# SCH_HackPack_2024-05-12.net
KiCad netlist of a schematic drawn in EasyEDA
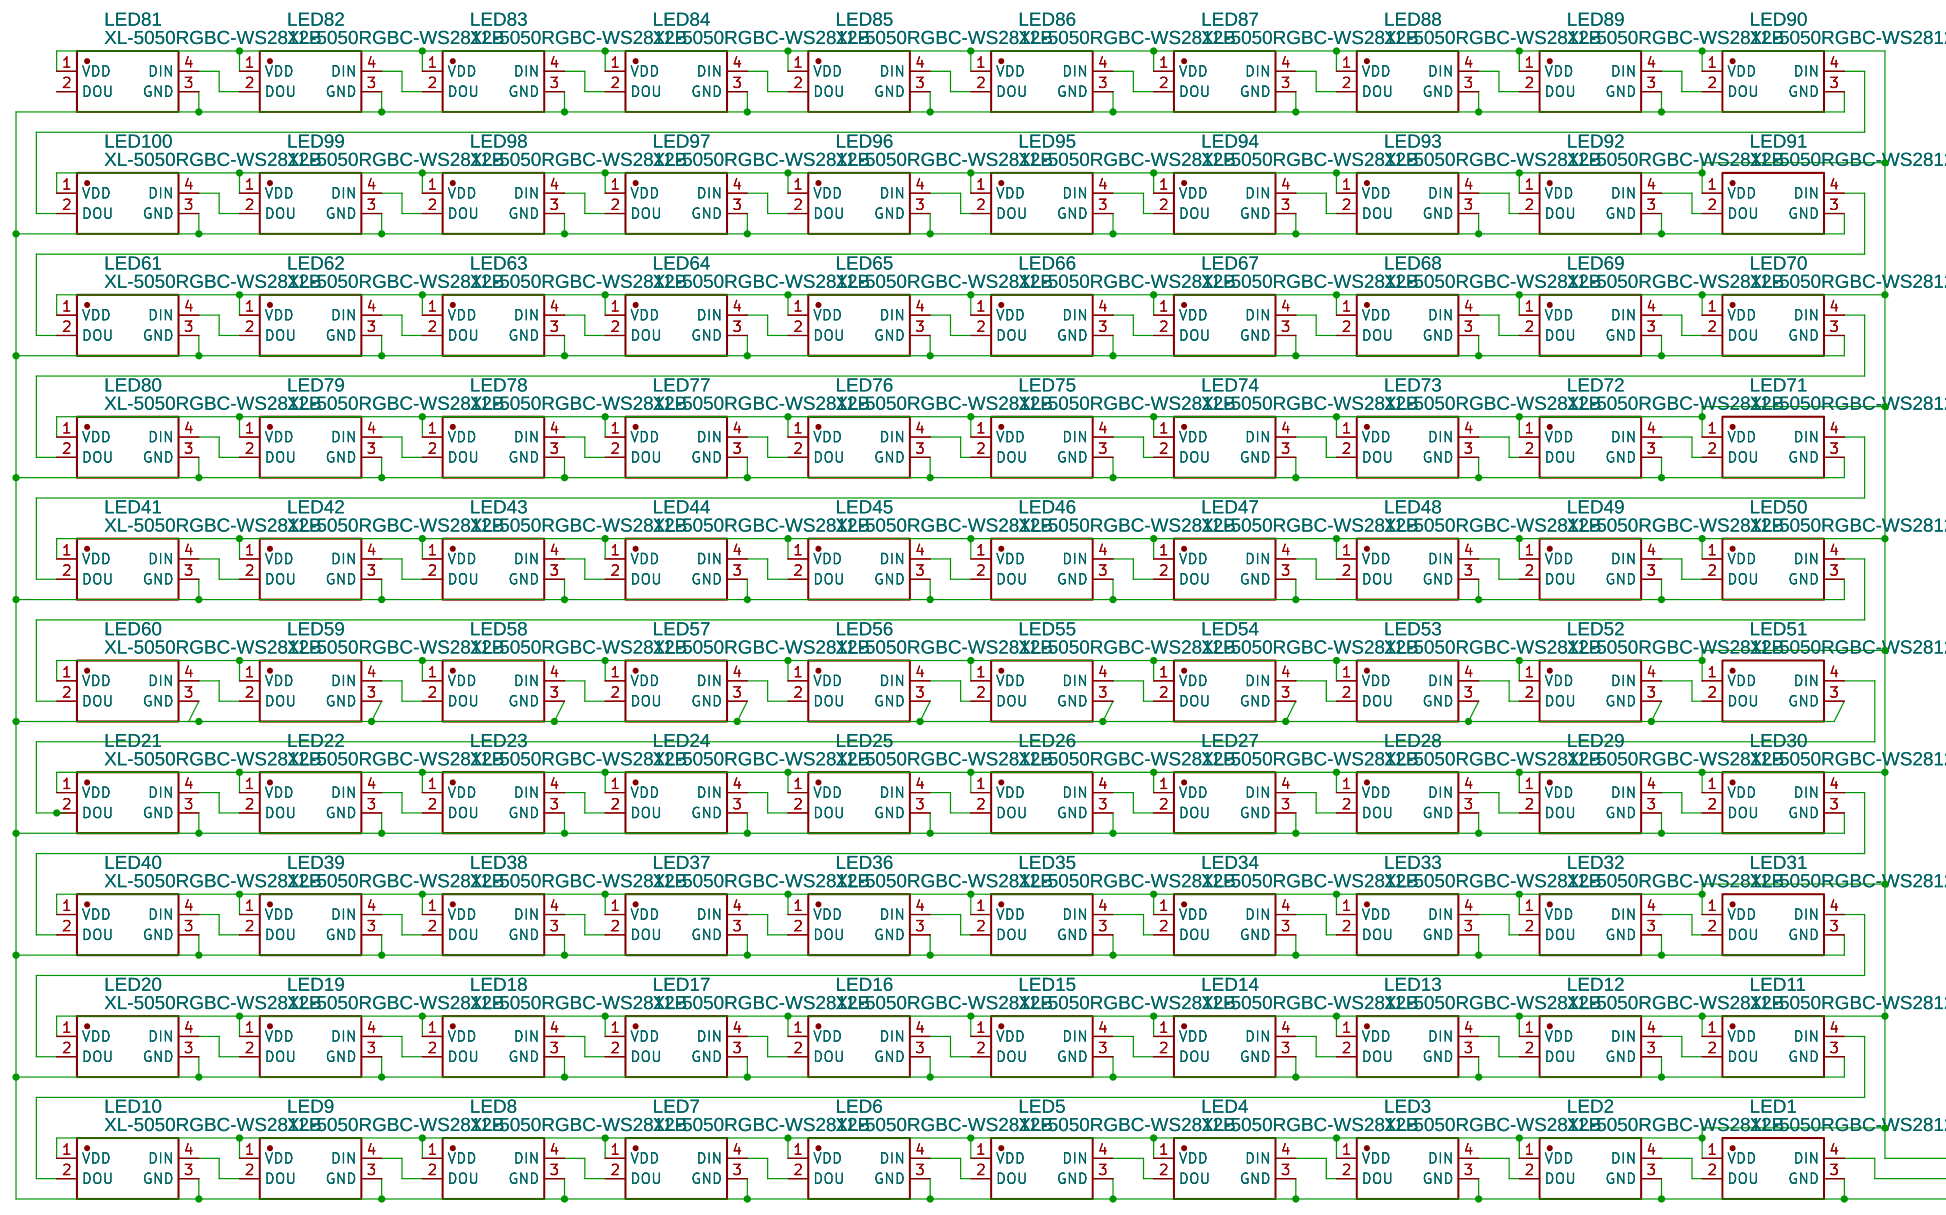
[diagram p0: schematic sheet]

(export (version "E")
  (design (tool "Eeschema 10.0.6"))
  (components
    (comp (ref "LED1")
      (value "XL-5050RGBC-WS2812B")
      (fields (field (name "Manufacturer") "XINGLIGHT(成兴光)"))
      (libsource (lib "") (part "XL-5050RGBC-WS2812B"))
    )
    (comp (ref "LED2")
      (value "XL-5050RGBC-WS2812B")
      (fields (field (name "Manufacturer") "XINGLIGHT(成兴光)"))
      (libsource (lib "") (part "XL-5050RGBC-WS2812B"))
    )
    (comp (ref "LED3")
      (value "XL-5050RGBC-WS2812B")
      (fields (field (name "Manufacturer") "XINGLIGHT(成兴光)"))
      (libsource (lib "") (part "XL-5050RGBC-WS2812B"))
    )
    (comp (ref "LED4")
      (value "XL-5050RGBC-WS2812B")
      (fields (field (name "Manufacturer") "XINGLIGHT(成兴光)"))
      (libsource (lib "") (part "XL-5050RGBC-WS2812B"))
    )
    (comp (ref "LED5")
      (value "XL-5050RGBC-WS2812B")
      (fields (field (name "Manufacturer") "XINGLIGHT(成兴光)"))
      (libsource (lib "") (part "XL-5050RGBC-WS2812B"))
    )
    (comp (ref "LED6")
      (value "XL-5050RGBC-WS2812B")
      (fields (field (name "Manufacturer") "XINGLIGHT(成兴光)"))
      (libsource (lib "") (part "XL-5050RGBC-WS2812B"))
    )
    (comp (ref "LED7")
      (value "XL-5050RGBC-WS2812B")
      (fields (field (name "Manufacturer") "XINGLIGHT(成兴光)"))
      (libsource (lib "") (part "XL-5050RGBC-WS2812B"))
    )
    (comp (ref "LED8")
      (value "XL-5050RGBC-WS2812B")
      (fields (field (name "Manufacturer") "XINGLIGHT(成兴光)"))
      (libsource (lib "") (part "XL-5050RGBC-WS2812B"))
    )
    (comp (ref "LED9")
      (value "XL-5050RGBC-WS2812B")
      (fields (field (name "Manufacturer") "XINGLIGHT(成兴光)"))
      (libsource (lib "") (part "XL-5050RGBC-WS2812B"))
    )
    (comp (ref "LED10")
      (value "XL-5050RGBC-WS2812B")
      (fields (field (name "Manufacturer") "XINGLIGHT(成兴光)"))
      (libsource (lib "") (part "XL-5050RGBC-WS2812B"))
    )
    (comp (ref "LED11")
      (value "XL-5050RGBC-WS2812B")
      (fields (field (name "Manufacturer") "XINGLIGHT(成兴光)"))
      (libsource (lib "") (part "XL-5050RGBC-WS2812B"))
    )
    (comp (ref "LED12")
      (value "XL-5050RGBC-WS2812B")
      (fields (field (name "Manufacturer") "XINGLIGHT(成兴光)"))
      (libsource (lib "") (part "XL-5050RGBC-WS2812B"))
    )
    (comp (ref "LED13")
      (value "XL-5050RGBC-WS2812B")
      (fields (field (name "Manufacturer") "XINGLIGHT(成兴光)"))
      (libsource (lib "") (part "XL-5050RGBC-WS2812B"))
    )
    (comp (ref "LED14")
      (value "XL-5050RGBC-WS2812B")
      (fields (field (name "Manufacturer") "XINGLIGHT(成兴光)"))
      (libsource (lib "") (part "XL-5050RGBC-WS2812B"))
    )
    (comp (ref "LED15")
      (value "XL-5050RGBC-WS2812B")
      (fields (field (name "Manufacturer") "XINGLIGHT(成兴光)"))
      (libsource (lib "") (part "XL-5050RGBC-WS2812B"))
    )
    (comp (ref "LED16")
      (value "XL-5050RGBC-WS2812B")
      (fields (field (name "Manufacturer") "XINGLIGHT(成兴光)"))
      (libsource (lib "") (part "XL-5050RGBC-WS2812B"))
    )
    (comp (ref "LED17")
      (value "XL-5050RGBC-WS2812B")
      (fields (field (name "Manufacturer") "XINGLIGHT(成兴光)"))
      (libsource (lib "") (part "XL-5050RGBC-WS2812B"))
    )
    (comp (ref "LED18")
      (value "XL-5050RGBC-WS2812B")
      (fields (field (name "Manufacturer") "XINGLIGHT(成兴光)"))
      (libsource (lib "") (part "XL-5050RGBC-WS2812B"))
    )
    (comp (ref "LED19")
      (value "XL-5050RGBC-WS2812B")
      (fields (field (name "Manufacturer") "XINGLIGHT(成兴光)"))
      (libsource (lib "") (part "XL-5050RGBC-WS2812B"))
    )
    (comp (ref "LED20")
      (value "XL-5050RGBC-WS2812B")
      (fields (field (name "Manufacturer") "XINGLIGHT(成兴光)"))
      (libsource (lib "") (part "XL-5050RGBC-WS2812B"))
    )
    (comp (ref "LED21")
      (value "XL-5050RGBC-WS2812B")
      (fields (field (name "Manufacturer") "XINGLIGHT(成兴光)"))
      (libsource (lib "") (part "XL-5050RGBC-WS2812B"))
    )
    (comp (ref "LED22")
      (value "XL-5050RGBC-WS2812B")
      (fields (field (name "Manufacturer") "XINGLIGHT(成兴光)"))
      (libsource (lib "") (part "XL-5050RGBC-WS2812B"))
    )
    (comp (ref "LED23")
      (value "XL-5050RGBC-WS2812B")
      (fields (field (name "Manufacturer") "XINGLIGHT(成兴光)"))
      (libsource (lib "") (part "XL-5050RGBC-WS2812B"))
    )
    (comp (ref "LED24")
      (value "XL-5050RGBC-WS2812B")
      (fields (field (name "Manufacturer") "XINGLIGHT(成兴光)"))
      (libsource (lib "") (part "XL-5050RGBC-WS2812B"))
    )
    (comp (ref "LED25")
      (value "XL-5050RGBC-WS2812B")
      (fields (field (name "Manufacturer") "XINGLIGHT(成兴光)"))
      (libsource (lib "") (part "XL-5050RGBC-WS2812B"))
    )
    (comp (ref "LED26")
      (value "XL-5050RGBC-WS2812B")
      (fields (field (name "Manufacturer") "XINGLIGHT(成兴光)"))
      (libsource (lib "") (part "XL-5050RGBC-WS2812B"))
    )
    (comp (ref "LED27")
      (value "XL-5050RGBC-WS2812B")
      (fields (field (name "Manufacturer") "XINGLIGHT(成兴光)"))
      (libsource (lib "") (part "XL-5050RGBC-WS2812B"))
    )
    (comp (ref "LED28")
      (value "XL-5050RGBC-WS2812B")
      (fields (field (name "Manufacturer") "XINGLIGHT(成兴光)"))
      (libsource (lib "") (part "XL-5050RGBC-WS2812B"))
    )
    (comp (ref "LED29")
      (value "XL-5050RGBC-WS2812B")
      (fields (field (name "Manufacturer") "XINGLIGHT(成兴光)"))
      (libsource (lib "") (part "XL-5050RGBC-WS2812B"))
    )
    (comp (ref "LED30")
      (value "XL-5050RGBC-WS2812B")
      (fields (field (name "Manufacturer") "XINGLIGHT(成兴光)"))
      (libsource (lib "") (part "XL-5050RGBC-WS2812B"))
    )
    (comp (ref "LED31")
      (value "XL-5050RGBC-WS2812B")
      (fields (field (name "Manufacturer") "XINGLIGHT(成兴光)"))
      (libsource (lib "") (part "XL-5050RGBC-WS2812B"))
    )
    (comp (ref "LED32")
      (value "XL-5050RGBC-WS2812B")
      (fields (field (name "Manufacturer") "XINGLIGHT(成兴光)"))
      (libsource (lib "") (part "XL-5050RGBC-WS2812B"))
    )
    (comp (ref "LED33")
      (value "XL-5050RGBC-WS2812B")
      (fields (field (name "Manufacturer") "XINGLIGHT(成兴光)"))
      (libsource (lib "") (part "XL-5050RGBC-WS2812B"))
    )
    (comp (ref "LED34")
      (value "XL-5050RGBC-WS2812B")
      (fields (field (name "Manufacturer") "XINGLIGHT(成兴光)"))
      (libsource (lib "") (part "XL-5050RGBC-WS2812B"))
    )
    (comp (ref "LED35")
      (value "XL-5050RGBC-WS2812B")
      (fields (field (name "Manufacturer") "XINGLIGHT(成兴光)"))
      (libsource (lib "") (part "XL-5050RGBC-WS2812B"))
    )
    (comp (ref "LED36")
      (value "XL-5050RGBC-WS2812B")
      (fields (field (name "Manufacturer") "XINGLIGHT(成兴光)"))
      (libsource (lib "") (part "XL-5050RGBC-WS2812B"))
    )
    (comp (ref "LED37")
      (value "XL-5050RGBC-WS2812B")
      (fields (field (name "Manufacturer") "XINGLIGHT(成兴光)"))
      (libsource (lib "") (part "XL-5050RGBC-WS2812B"))
    )
    (comp (ref "LED38")
      (value "XL-5050RGBC-WS2812B")
      (fields (field (name "Manufacturer") "XINGLIGHT(成兴光)"))
      (libsource (lib "") (part "XL-5050RGBC-WS2812B"))
    )
    (comp (ref "LED39")
      (value "XL-5050RGBC-WS2812B")
      (fields (field (name "Manufacturer") "XINGLIGHT(成兴光)"))
      (libsource (lib "") (part "XL-5050RGBC-WS2812B"))
    )
    (comp (ref "LED40")
      (value "XL-5050RGBC-WS2812B")
      (fields (field (name "Manufacturer") "XINGLIGHT(成兴光)"))
      (libsource (lib "") (part "XL-5050RGBC-WS2812B"))
    )
    (comp (ref "LED41")
      (value "XL-5050RGBC-WS2812B")
      (fields (field (name "Manufacturer") "XINGLIGHT(成兴光)"))
      (libsource (lib "") (part "XL-5050RGBC-WS2812B"))
    )
    (comp (ref "LED42")
      (value "XL-5050RGBC-WS2812B")
      (fields (field (name "Manufacturer") "XINGLIGHT(成兴光)"))
      (libsource (lib "") (part "XL-5050RGBC-WS2812B"))
    )
    (comp (ref "LED43")
      (value "XL-5050RGBC-WS2812B")
      (fields (field (name "Manufacturer") "XINGLIGHT(成兴光)"))
      (libsource (lib "") (part "XL-5050RGBC-WS2812B"))
    )
    (comp (ref "LED44")
      (value "XL-5050RGBC-WS2812B")
      (fields (field (name "Manufacturer") "XINGLIGHT(成兴光)"))
      (libsource (lib "") (part "XL-5050RGBC-WS2812B"))
    )
    (comp (ref "LED45")
      (value "XL-5050RGBC-WS2812B")
      (fields (field (name "Manufacturer") "XINGLIGHT(成兴光)"))
      (libsource (lib "") (part "XL-5050RGBC-WS2812B"))
    )
    (comp (ref "LED46")
      (value "XL-5050RGBC-WS2812B")
      (fields (field (name "Manufacturer") "XINGLIGHT(成兴光)"))
      (libsource (lib "") (part "XL-5050RGBC-WS2812B"))
    )
    (comp (ref "LED47")
      (value "XL-5050RGBC-WS2812B")
      (fields (field (name "Manufacturer") "XINGLIGHT(成兴光)"))
      (libsource (lib "") (part "XL-5050RGBC-WS2812B"))
    )
    (comp (ref "LED48")
      (value "XL-5050RGBC-WS2812B")
      (fields (field (name "Manufacturer") "XINGLIGHT(成兴光)"))
      (libsource (lib "") (part "XL-5050RGBC-WS2812B"))
    )
    (comp (ref "LED49")
      (value "XL-5050RGBC-WS2812B")
      (fields (field (name "Manufacturer") "XINGLIGHT(成兴光)"))
      (libsource (lib "") (part "XL-5050RGBC-WS2812B"))
    )
    (comp (ref "LED50")
      (value "XL-5050RGBC-WS2812B")
      (fields (field (name "Manufacturer") "XINGLIGHT(成兴光)"))
      (libsource (lib "") (part "XL-5050RGBC-WS2812B"))
    )
    (comp (ref "LED51")
      (value "XL-5050RGBC-WS2812B")
      (fields (field (name "Manufacturer") "XINGLIGHT(成兴光)"))
      (libsource (lib "") (part "XL-5050RGBC-WS2812B"))
    )
    (comp (ref "LED52")
      (value "XL-5050RGBC-WS2812B")
      (fields (field (name "Manufacturer") "XINGLIGHT(成兴光)"))
      (libsource (lib "") (part "XL-5050RGBC-WS2812B"))
    )
    (comp (ref "LED53")
      (value "XL-5050RGBC-WS2812B")
      (fields (field (name "Manufacturer") "XINGLIGHT(成兴光)"))
      (libsource (lib "") (part "XL-5050RGBC-WS2812B"))
    )
    (comp (ref "LED54")
      (value "XL-5050RGBC-WS2812B")
      (fields (field (name "Manufacturer") "XINGLIGHT(成兴光)"))
      (libsource (lib "") (part "XL-5050RGBC-WS2812B"))
    )
    (comp (ref "LED55")
      (value "XL-5050RGBC-WS2812B")
      (fields (field (name "Manufacturer") "XINGLIGHT(成兴光)"))
      (libsource (lib "") (part "XL-5050RGBC-WS2812B"))
    )
    (comp (ref "LED56")
      (value "XL-5050RGBC-WS2812B")
      (fields (field (name "Manufacturer") "XINGLIGHT(成兴光)"))
      (libsource (lib "") (part "XL-5050RGBC-WS2812B"))
    )
    (comp (ref "LED57")
      (value "XL-5050RGBC-WS2812B")
      (fields (field (name "Manufacturer") "XINGLIGHT(成兴光)"))
      (libsource (lib "") (part "XL-5050RGBC-WS2812B"))
    )
    (comp (ref "LED58")
      (value "XL-5050RGBC-WS2812B")
      (fields (field (name "Manufacturer") "XINGLIGHT(成兴光)"))
      (libsource (lib "") (part "XL-5050RGBC-WS2812B"))
    )
    (comp (ref "LED59")
      (value "XL-5050RGBC-WS2812B")
      (fields (field (name "Manufacturer") "XINGLIGHT(成兴光)"))
      (libsource (lib "") (part "XL-5050RGBC-WS2812B"))
    )
    (comp (ref "LED60")
      (value "XL-5050RGBC-WS2812B")
      (fields (field (name "Manufacturer") "XINGLIGHT(成兴光)"))
      (libsource (lib "") (part "XL-5050RGBC-WS2812B"))
    )
    (comp (ref "LED61")
      (value "XL-5050RGBC-WS2812B")
      (fields (field (name "Manufacturer") "XINGLIGHT(成兴光)"))
      (libsource (lib "") (part "XL-5050RGBC-WS2812B"))
    )
    (comp (ref "LED62")
      (value "XL-5050RGBC-WS2812B")
      (fields (field (name "Manufacturer") "XINGLIGHT(成兴光)"))
      (libsource (lib "") (part "XL-5050RGBC-WS2812B"))
    )
    (comp (ref "LED63")
      (value "XL-5050RGBC-WS2812B")
      (fields (field (name "Manufacturer") "XINGLIGHT(成兴光)"))
      (libsource (lib "") (part "XL-5050RGBC-WS2812B"))
    )
    (comp (ref "LED64")
      (value "XL-5050RGBC-WS2812B")
      (fields (field (name "Manufacturer") "XINGLIGHT(成兴光)"))
      (libsource (lib "") (part "XL-5050RGBC-WS2812B"))
    )
    (comp (ref "LED65")
      (value "XL-5050RGBC-WS2812B")
      (fields (field (name "Manufacturer") "XINGLIGHT(成兴光)"))
      (libsource (lib "") (part "XL-5050RGBC-WS2812B"))
    )
    (comp (ref "LED66")
      (value "XL-5050RGBC-WS2812B")
      (fields (field (name "Manufacturer") "XINGLIGHT(成兴光)"))
      (libsource (lib "") (part "XL-5050RGBC-WS2812B"))
    )
    (comp (ref "LED67")
      (value "XL-5050RGBC-WS2812B")
      (fields (field (name "Manufacturer") "XINGLIGHT(成兴光)"))
      (libsource (lib "") (part "XL-5050RGBC-WS2812B"))
    )
    (comp (ref "LED68")
      (value "XL-5050RGBC-WS2812B")
      (fields (field (name "Manufacturer") "XINGLIGHT(成兴光)"))
      (libsource (lib "") (part "XL-5050RGBC-WS2812B"))
    )
    (comp (ref "LED69")
      (value "XL-5050RGBC-WS2812B")
      (fields (field (name "Manufacturer") "XINGLIGHT(成兴光)"))
      (libsource (lib "") (part "XL-5050RGBC-WS2812B"))
    )
    (comp (ref "LED70")
      (value "XL-5050RGBC-WS2812B")
      (fields (field (name "Manufacturer") "XINGLIGHT(成兴光)"))
      (libsource (lib "") (part "XL-5050RGBC-WS2812B"))
    )
    (comp (ref "LED71")
      (value "XL-5050RGBC-WS2812B")
      (fields (field (name "Manufacturer") "XINGLIGHT(成兴光)"))
      (libsource (lib "") (part "XL-5050RGBC-WS2812B"))
    )
    (comp (ref "LED72")
      (value "XL-5050RGBC-WS2812B")
      (fields (field (name "Manufacturer") "XINGLIGHT(成兴光)"))
      (libsource (lib "") (part "XL-5050RGBC-WS2812B"))
    )
    (comp (ref "LED73")
      (value "XL-5050RGBC-WS2812B")
      (fields (field (name "Manufacturer") "XINGLIGHT(成兴光)"))
      (libsource (lib "") (part "XL-5050RGBC-WS2812B"))
    )
    (comp (ref "LED74")
      (value "XL-5050RGBC-WS2812B")
      (fields (field (name "Manufacturer") "XINGLIGHT(成兴光)"))
      (libsource (lib "") (part "XL-5050RGBC-WS2812B"))
    )
    (comp (ref "LED75")
      (value "XL-5050RGBC-WS2812B")
      (fields (field (name "Manufacturer") "XINGLIGHT(成兴光)"))
      (libsource (lib "") (part "XL-5050RGBC-WS2812B"))
    )
    (comp (ref "LED76")
      (value "XL-5050RGBC-WS2812B")
      (fields (field (name "Manufacturer") "XINGLIGHT(成兴光)"))
      (libsource (lib "") (part "XL-5050RGBC-WS2812B"))
    )
    (comp (ref "LED77")
      (value "XL-5050RGBC-WS2812B")
      (fields (field (name "Manufacturer") "XINGLIGHT(成兴光)"))
      (libsource (lib "") (part "XL-5050RGBC-WS2812B"))
    )
    (comp (ref "LED78")
      (value "XL-5050RGBC-WS2812B")
      (fields (field (name "Manufacturer") "XINGLIGHT(成兴光)"))
      (libsource (lib "") (part "XL-5050RGBC-WS2812B"))
    )
    (comp (ref "LED79")
      (value "XL-5050RGBC-WS2812B")
      (fields (field (name "Manufacturer") "XINGLIGHT(成兴光)"))
      (libsource (lib "") (part "XL-5050RGBC-WS2812B"))
    )
    (comp (ref "LED80")
      (value "XL-5050RGBC-WS2812B")
      (fields (field (name "Manufacturer") "XINGLIGHT(成兴光)"))
      (libsource (lib "") (part "XL-5050RGBC-WS2812B"))
    )
    (comp (ref "LED81")
      (value "XL-5050RGBC-WS2812B")
      (fields (field (name "Manufacturer") "XINGLIGHT(成兴光)"))
      (libsource (lib "") (part "XL-5050RGBC-WS2812B"))
    )
    (comp (ref "LED82")
      (value "XL-5050RGBC-WS2812B")
      (fields (field (name "Manufacturer") "XINGLIGHT(成兴光)"))
      (libsource (lib "") (part "XL-5050RGBC-WS2812B"))
    )
    (comp (ref "LED83")
      (value "XL-5050RGBC-WS2812B")
      (fields (field (name "Manufacturer") "XINGLIGHT(成兴光)"))
      (libsource (lib "") (part "XL-5050RGBC-WS2812B"))
    )
    (comp (ref "LED84")
      (value "XL-5050RGBC-WS2812B")
      (fields (field (name "Manufacturer") "XINGLIGHT(成兴光)"))
      (libsource (lib "") (part "XL-5050RGBC-WS2812B"))
    )
    (comp (ref "LED85")
      (value "XL-5050RGBC-WS2812B")
      (fields (field (name "Manufacturer") "XINGLIGHT(成兴光)"))
      (libsource (lib "") (part "XL-5050RGBC-WS2812B"))
    )
    (comp (ref "LED86")
      (value "XL-5050RGBC-WS2812B")
      (fields (field (name "Manufacturer") "XINGLIGHT(成兴光)"))
      (libsource (lib "") (part "XL-5050RGBC-WS2812B"))
    )
    (comp (ref "LED87")
      (value "XL-5050RGBC-WS2812B")
      (fields (field (name "Manufacturer") "XINGLIGHT(成兴光)"))
      (libsource (lib "") (part "XL-5050RGBC-WS2812B"))
    )
    (comp (ref "LED88")
      (value "XL-5050RGBC-WS2812B")
      (fields (field (name "Manufacturer") "XINGLIGHT(成兴光)"))
      (libsource (lib "") (part "XL-5050RGBC-WS2812B"))
    )
    (comp (ref "LED89")
      (value "XL-5050RGBC-WS2812B")
      (fields (field (name "Manufacturer") "XINGLIGHT(成兴光)"))
      (libsource (lib "") (part "XL-5050RGBC-WS2812B"))
    )
    (comp (ref "LED90")
      (value "XL-5050RGBC-WS2812B")
      (fields (field (name "Manufacturer") "XINGLIGHT(成兴光)"))
      (libsource (lib "") (part "XL-5050RGBC-WS2812B"))
    )
    (comp (ref "LED91")
      (value "XL-5050RGBC-WS2812B")
      (fields (field (name "Manufacturer") "XINGLIGHT(成兴光)"))
      (libsource (lib "") (part "XL-5050RGBC-WS2812B"))
    )
    (comp (ref "LED92")
      (value "XL-5050RGBC-WS2812B")
      (fields (field (name "Manufacturer") "XINGLIGHT(成兴光)"))
      (libsource (lib "") (part "XL-5050RGBC-WS2812B"))
    )
    (comp (ref "LED93")
      (value "XL-5050RGBC-WS2812B")
      (fields (field (name "Manufacturer") "XINGLIGHT(成兴光)"))
      (libsource (lib "") (part "XL-5050RGBC-WS2812B"))
    )
    (comp (ref "LED94")
      (value "XL-5050RGBC-WS2812B")
      (fields (field (name "Manufacturer") "XINGLIGHT(成兴光)"))
      (libsource (lib "") (part "XL-5050RGBC-WS2812B"))
    )
    (comp (ref "LED95")
      (value "XL-5050RGBC-WS2812B")
      (fields (field (name "Manufacturer") "XINGLIGHT(成兴光)"))
      (libsource (lib "") (part "XL-5050RGBC-WS2812B"))
    )
    (comp (ref "LED96")
      (value "XL-5050RGBC-WS2812B")
      (fields (field (name "Manufacturer") "XINGLIGHT(成兴光)"))
      (libsource (lib "") (part "XL-5050RGBC-WS2812B"))
    )
    (comp (ref "LED97")
      (value "XL-5050RGBC-WS2812B")
      (fields (field (name "Manufacturer") "XINGLIGHT(成兴光)"))
      (libsource (lib "") (part "XL-5050RGBC-WS2812B"))
    )
    (comp (ref "LED98")
      (value "XL-5050RGBC-WS2812B")
      (fields (field (name "Manufacturer") "XINGLIGHT(成兴光)"))
      (libsource (lib "") (part "XL-5050RGBC-WS2812B"))
    )
    (comp (ref "LED99")
      (value "XL-5050RGBC-WS2812B")
      (fields (field (name "Manufacturer") "XINGLIGHT(成兴光)"))
      (libsource (lib "") (part "XL-5050RGBC-WS2812B"))
    )
    (comp (ref "LED100")
      (value "XL-5050RGBC-WS2812B")
      (fields (field (name "Manufacturer") "XINGLIGHT(成兴光)"))
      (libsource (lib "") (part "XL-5050RGBC-WS2812B"))
    )
  )
  (nets
    (net (code "1") (name "Net-(LED1-DOU)") (class "Default")
      (node (ref "LED1") (pin "2") (pinfunction "DOU_2") (pintype "unspecified"))
      (node (ref "LED2") (pin "4") (pinfunction "DIN_4") (pintype "unspecified"))
    )
    (net (code "2") (name "Net-(LED1-GND)") (class "Default")
      (node (ref "LED1") (pin "3") (pinfunction "GND_3") (pintype "unspecified"))
      (node (ref "LED10") (pin "3") (pinfunction "GND_3") (pintype "unspecified"))
      (node (ref "LED100") (pin "3") (pinfunction "GND_3") (pintype "unspecified"))
      (node (ref "LED11") (pin "3") (pinfunction "GND_3") (pintype "unspecified"))
      (node (ref "LED12") (pin "3") (pinfunction "GND_3") (pintype "unspecified"))
      (node (ref "LED13") (pin "3") (pinfunction "GND_3") (pintype "unspecified"))
      (node (ref "LED14") (pin "3") (pinfunction "GND_3") (pintype "unspecified"))
      (node (ref "LED15") (pin "3") (pinfunction "GND_3") (pintype "unspecified"))
      (node (ref "LED16") (pin "3") (pinfunction "GND_3") (pintype "unspecified"))
      (node (ref "LED17") (pin "3") (pinfunction "GND_3") (pintype "unspecified"))
      (node (ref "LED18") (pin "3") (pinfunction "GND_3") (pintype "unspecified"))
      (node (ref "LED19") (pin "3") (pinfunction "GND_3") (pintype "unspecified"))
      (node (ref "LED2") (pin "3") (pinfunction "GND_3") (pintype "unspecified"))
      (node (ref "LED20") (pin "3") (pinfunction "GND_3") (pintype "unspecified"))
      (node (ref "LED21") (pin "3") (pinfunction "GND_3") (pintype "unspecified"))
      (node (ref "LED22") (pin "3") (pinfunction "GND_3") (pintype "unspecified"))
      (node (ref "LED23") (pin "3") (pinfunction "GND_3") (pintype "unspecified"))
      (node (ref "LED24") (pin "3") (pinfunction "GND_3") (pintype "unspecified"))
      (node (ref "LED25") (pin "3") (pinfunction "GND_3") (pintype "unspecified"))
      (node (ref "LED26") (pin "3") (pinfunction "GND_3") (pintype "unspecified"))
      (node (ref "LED27") (pin "3") (pinfunction "GND_3") (pintype "unspecified"))
      (node (ref "LED28") (pin "3") (pinfunction "GND_3") (pintype "unspecified"))
      (node (ref "LED29") (pin "3") (pinfunction "GND_3") (pintype "unspecified"))
      (node (ref "LED3") (pin "3") (pinfunction "GND_3") (pintype "unspecified"))
      (node (ref "LED30") (pin "3") (pinfunction "GND_3") (pintype "unspecified"))
      (node (ref "LED31") (pin "3") (pinfunction "GND_3") (pintype "unspecified"))
      (node (ref "LED32") (pin "3") (pinfunction "GND_3") (pintype "unspecified"))
      (node (ref "LED33") (pin "3") (pinfunction "GND_3") (pintype "unspecified"))
      (node (ref "LED34") (pin "3") (pinfunction "GND_3") (pintype "unspecified"))
      (node (ref "LED35") (pin "3") (pinfunction "GND_3") (pintype "unspecified"))
      (node (ref "LED36") (pin "3") (pinfunction "GND_3") (pintype "unspecified"))
      (node (ref "LED37") (pin "3") (pinfunction "GND_3") (pintype "unspecified"))
      (node (ref "LED38") (pin "3") (pinfunction "GND_3") (pintype "unspecified"))
      (node (ref "LED39") (pin "3") (pinfunction "GND_3") (pintype "unspecified"))
      (node (ref "LED4") (pin "3") (pinfunction "GND_3") (pintype "unspecified"))
      (node (ref "LED40") (pin "3") (pinfunction "GND_3") (pintype "unspecified"))
      (node (ref "LED41") (pin "3") (pinfunction "GND_3") (pintype "unspecified"))
      (node (ref "LED42") (pin "3") (pinfunction "GND_3") (pintype "unspecified"))
      (node (ref "LED43") (pin "3") (pinfunction "GND_3") (pintype "unspecified"))
      (node (ref "LED44") (pin "3") (pinfunction "GND_3") (pintype "unspecified"))
      (node (ref "LED45") (pin "3") (pinfunction "GND_3") (pintype "unspecified"))
      (node (ref "LED46") (pin "3") (pinfunction "GND_3") (pintype "unspecified"))
      (node (ref "LED47") (pin "3") (pinfunction "GND_3") (pintype "unspecified"))
      (node (ref "LED48") (pin "3") (pinfunction "GND_3") (pintype "unspecified"))
      (node (ref "LED49") (pin "3") (pinfunction "GND_3") (pintype "unspecified"))
      (node (ref "LED5") (pin "3") (pinfunction "GND_3") (pintype "unspecified"))
      (node (ref "LED50") (pin "3") (pinfunction "GND_3") (pintype "unspecified"))
      (node (ref "LED51") (pin "3") (pinfunction "GND_3") (pintype "unspecified"))
      (node (ref "LED52") (pin "3") (pinfunction "GND_3") (pintype "unspecified"))
      (node (ref "LED53") (pin "3") (pinfunction "GND_3") (pintype "unspecified"))
      (node (ref "LED54") (pin "3") (pinfunction "GND_3") (pintype "unspecified"))
      (node (ref "LED55") (pin "3") (pinfunction "GND_3") (pintype "unspecified"))
      (node (ref "LED56") (pin "3") (pinfunction "GND_3") (pintype "unspecified"))
      (node (ref "LED57") (pin "3") (pinfunction "GND_3") (pintype "unspecified"))
      (node (ref "LED58") (pin "3") (pinfunction "GND_3") (pintype "unspecified"))
      (node (ref "LED59") (pin "3") (pinfunction "GND_3") (pintype "unspecified"))
      (node (ref "LED6") (pin "3") (pinfunction "GND_3") (pintype "unspecified"))
      (node (ref "LED60") (pin "3") (pinfunction "GND_3") (pintype "unspecified"))
      (node (ref "LED61") (pin "3") (pinfunction "GND_3") (pintype "unspecified"))
      (node (ref "LED62") (pin "3") (pinfunction "GND_3") (pintype "unspecified"))
      (node (ref "LED63") (pin "3") (pinfunction "GND_3") (pintype "unspecified"))
      (node (ref "LED64") (pin "3") (pinfunction "GND_3") (pintype "unspecified"))
      (node (ref "LED65") (pin "3") (pinfunction "GND_3") (pintype "unspecified"))
      (node (ref "LED66") (pin "3") (pinfunction "GND_3") (pintype "unspecified"))
      (node (ref "LED67") (pin "3") (pinfunction "GND_3") (pintype "unspecified"))
      (node (ref "LED68") (pin "3") (pinfunction "GND_3") (pintype "unspecified"))
      (node (ref "LED69") (pin "3") (pinfunction "GND_3") (pintype "unspecified"))
      (node (ref "LED7") (pin "3") (pinfunction "GND_3") (pintype "unspecified"))
      (node (ref "LED70") (pin "3") (pinfunction "GND_3") (pintype "unspecified"))
      (node (ref "LED71") (pin "3") (pinfunction "GND_3") (pintype "unspecified"))
      (node (ref "LED72") (pin "3") (pinfunction "GND_3") (pintype "unspecified"))
      (node (ref "LED73") (pin "3") (pinfunction "GND_3") (pintype "unspecified"))
      (node (ref "LED74") (pin "3") (pinfunction "GND_3") (pintype "unspecified"))
      (node (ref "LED75") (pin "3") (pinfunction "GND_3") (pintype "unspecified"))
      (node (ref "LED76") (pin "3") (pinfunction "GND_3") (pintype "unspecified"))
      (node (ref "LED77") (pin "3") (pinfunction "GND_3") (pintype "unspecified"))
      (node (ref "LED78") (pin "3") (pinfunction "GND_3") (pintype "unspecified"))
      (node (ref "LED79") (pin "3") (pinfunction "GND_3") (pintype "unspecified"))
      (node (ref "LED8") (pin "3") (pinfunction "GND_3") (pintype "unspecified"))
      (node (ref "LED80") (pin "3") (pinfunction "GND_3") (pintype "unspecified"))
      (node (ref "LED81") (pin "3") (pinfunction "GND_3") (pintype "unspecified"))
      (node (ref "LED82") (pin "3") (pinfunction "GND_3") (pintype "unspecified"))
      (node (ref "LED83") (pin "3") (pinfunction "GND_3") (pintype "unspecified"))
      (node (ref "LED84") (pin "3") (pinfunction "GND_3") (pintype "unspecified"))
      (node (ref "LED85") (pin "3") (pinfunction "GND_3") (pintype "unspecified"))
      (node (ref "LED86") (pin "3") (pinfunction "GND_3") (pintype "unspecified"))
      (node (ref "LED87") (pin "3") (pinfunction "GND_3") (pintype "unspecified"))
      (node (ref "LED88") (pin "3") (pinfunction "GND_3") (pintype "unspecified"))
      (node (ref "LED89") (pin "3") (pinfunction "GND_3") (pintype "unspecified"))
      (node (ref "LED9") (pin "3") (pinfunction "GND_3") (pintype "unspecified"))
      (node (ref "LED90") (pin "3") (pinfunction "GND_3") (pintype "unspecified"))
      (node (ref "LED91") (pin "3") (pinfunction "GND_3") (pintype "unspecified"))
      (node (ref "LED92") (pin "3") (pinfunction "GND_3") (pintype "unspecified"))
      (node (ref "LED93") (pin "3") (pinfunction "GND_3") (pintype "unspecified"))
      (node (ref "LED94") (pin "3") (pinfunction "GND_3") (pintype "unspecified"))
      (node (ref "LED95") (pin "3") (pinfunction "GND_3") (pintype "unspecified"))
      (node (ref "LED96") (pin "3") (pinfunction "GND_3") (pintype "unspecified"))
      (node (ref "LED97") (pin "3") (pinfunction "GND_3") (pintype "unspecified"))
      (node (ref "LED98") (pin "3") (pinfunction "GND_3") (pintype "unspecified"))
      (node (ref "LED99") (pin "3") (pinfunction "GND_3") (pintype "unspecified"))
    )
    (net (code "3") (name "Net-(LED1-VDD)") (class "Default")
      (node (ref "LED1") (pin "1") (pinfunction "VDD_1") (pintype "unspecified"))
      (node (ref "LED10") (pin "1") (pinfunction "VDD_1") (pintype "unspecified"))
      (node (ref "LED100") (pin "1") (pinfunction "VDD_1") (pintype "unspecified"))
      (node (ref "LED11") (pin "1") (pinfunction "VDD_1") (pintype "unspecified"))
      (node (ref "LED12") (pin "1") (pinfunction "VDD_1") (pintype "unspecified"))
      (node (ref "LED13") (pin "1") (pinfunction "VDD_1") (pintype "unspecified"))
      (node (ref "LED14") (pin "1") (pinfunction "VDD_1") (pintype "unspecified"))
      (node (ref "LED15") (pin "1") (pinfunction "VDD_1") (pintype "unspecified"))
      (node (ref "LED16") (pin "1") (pinfunction "VDD_1") (pintype "unspecified"))
      (node (ref "LED17") (pin "1") (pinfunction "VDD_1") (pintype "unspecified"))
      (node (ref "LED18") (pin "1") (pinfunction "VDD_1") (pintype "unspecified"))
      (node (ref "LED19") (pin "1") (pinfunction "VDD_1") (pintype "unspecified"))
      (node (ref "LED2") (pin "1") (pinfunction "VDD_1") (pintype "unspecified"))
      (node (ref "LED20") (pin "1") (pinfunction "VDD_1") (pintype "unspecified"))
      (node (ref "LED21") (pin "1") (pinfunction "VDD_1") (pintype "unspecified"))
      (node (ref "LED22") (pin "1") (pinfunction "VDD_1") (pintype "unspecified"))
      (node (ref "LED23") (pin "1") (pinfunction "VDD_1") (pintype "unspecified"))
      (node (ref "LED24") (pin "1") (pinfunction "VDD_1") (pintype "unspecified"))
      (node (ref "LED25") (pin "1") (pinfunction "VDD_1") (pintype "unspecified"))
      (node (ref "LED26") (pin "1") (pinfunction "VDD_1") (pintype "unspecified"))
      (node (ref "LED27") (pin "1") (pinfunction "VDD_1") (pintype "unspecified"))
      (node (ref "LED28") (pin "1") (pinfunction "VDD_1") (pintype "unspecified"))
      (node (ref "LED29") (pin "1") (pinfunction "VDD_1") (pintype "unspecified"))
      (node (ref "LED3") (pin "1") (pinfunction "VDD_1") (pintype "unspecified"))
      (node (ref "LED30") (pin "1") (pinfunction "VDD_1") (pintype "unspecified"))
      (node (ref "LED31") (pin "1") (pinfunction "VDD_1") (pintype "unspecified"))
      (node (ref "LED32") (pin "1") (pinfunction "VDD_1") (pintype "unspecified"))
      (node (ref "LED33") (pin "1") (pinfunction "VDD_1") (pintype "unspecified"))
      (node (ref "LED34") (pin "1") (pinfunction "VDD_1") (pintype "unspecified"))
      (node (ref "LED35") (pin "1") (pinfunction "VDD_1") (pintype "unspecified"))
      (node (ref "LED36") (pin "1") (pinfunction "VDD_1") (pintype "unspecified"))
      (node (ref "LED37") (pin "1") (pinfunction "VDD_1") (pintype "unspecified"))
      (node (ref "LED38") (pin "1") (pinfunction "VDD_1") (pintype "unspecified"))
      (node (ref "LED39") (pin "1") (pinfunction "VDD_1") (pintype "unspecified"))
      (node (ref "LED4") (pin "1") (pinfunction "VDD_1") (pintype "unspecified"))
      (node (ref "LED40") (pin "1") (pinfunction "VDD_1") (pintype "unspecified"))
      (node (ref "LED41") (pin "1") (pinfunction "VDD_1") (pintype "unspecified"))
      (node (ref "LED42") (pin "1") (pinfunction "VDD_1") (pintype "unspecified"))
      (node (ref "LED43") (pin "1") (pinfunction "VDD_1") (pintype "unspecified"))
      (node (ref "LED44") (pin "1") (pinfunction "VDD_1") (pintype "unspecified"))
      (node (ref "LED45") (pin "1") (pinfunction "VDD_1") (pintype "unspecified"))
      (node (ref "LED46") (pin "1") (pinfunction "VDD_1") (pintype "unspecified"))
      (node (ref "LED47") (pin "1") (pinfunction "VDD_1") (pintype "unspecified"))
      (node (ref "LED48") (pin "1") (pinfunction "VDD_1") (pintype "unspecified"))
      (node (ref "LED49") (pin "1") (pinfunction "VDD_1") (pintype "unspecified"))
      (node (ref "LED5") (pin "1") (pinfunction "VDD_1") (pintype "unspecified"))
      (node (ref "LED50") (pin "1") (pinfunction "VDD_1") (pintype "unspecified"))
      (node (ref "LED51") (pin "1") (pinfunction "VDD_1") (pintype "unspecified"))
      (node (ref "LED52") (pin "1") (pinfunction "VDD_1") (pintype "unspecified"))
      (node (ref "LED53") (pin "1") (pinfunction "VDD_1") (pintype "unspecified"))
      (node (ref "LED54") (pin "1") (pinfunction "VDD_1") (pintype "unspecified"))
      (node (ref "LED55") (pin "1") (pinfunction "VDD_1") (pintype "unspecified"))
      (node (ref "LED56") (pin "1") (pinfunction "VDD_1") (pintype "unspecified"))
      (node (ref "LED57") (pin "1") (pinfunction "VDD_1") (pintype "unspecified"))
      (node (ref "LED58") (pin "1") (pinfunction "VDD_1") (pintype "unspecified"))
      (node (ref "LED59") (pin "1") (pinfunction "VDD_1") (pintype "unspecified"))
      (node (ref "LED6") (pin "1") (pinfunction "VDD_1") (pintype "unspecified"))
      (node (ref "LED60") (pin "1") (pinfunction "VDD_1") (pintype "unspecified"))
      (node (ref "LED61") (pin "1") (pinfunction "VDD_1") (pintype "unspecified"))
      (node (ref "LED62") (pin "1") (pinfunction "VDD_1") (pintype "unspecified"))
      (node (ref "LED63") (pin "1") (pinfunction "VDD_1") (pintype "unspecified"))
      (node (ref "LED64") (pin "1") (pinfunction "VDD_1") (pintype "unspecified"))
      (node (ref "LED65") (pin "1") (pinfunction "VDD_1") (pintype "unspecified"))
      (node (ref "LED66") (pin "1") (pinfunction "VDD_1") (pintype "unspecified"))
      (node (ref "LED67") (pin "1") (pinfunction "VDD_1") (pintype "unspecified"))
      (node (ref "LED68") (pin "1") (pinfunction "VDD_1") (pintype "unspecified"))
      (node (ref "LED69") (pin "1") (pinfunction "VDD_1") (pintype "unspecified"))
      (node (ref "LED7") (pin "1") (pinfunction "VDD_1") (pintype "unspecified"))
      (node (ref "LED70") (pin "1") (pinfunction "VDD_1") (pintype "unspecified"))
      (node (ref "LED71") (pin "1") (pinfunction "VDD_1") (pintype "unspecified"))
      (node (ref "LED72") (pin "1") (pinfunction "VDD_1") (pintype "unspecified"))
      (node (ref "LED73") (pin "1") (pinfunction "VDD_1") (pintype "unspecified"))
      (node (ref "LED74") (pin "1") (pinfunction "VDD_1") (pintype "unspecified"))
      (node (ref "LED75") (pin "1") (pinfunction "VDD_1") (pintype "unspecified"))
      (node (ref "LED76") (pin "1") (pinfunction "VDD_1") (pintype "unspecified"))
      (node (ref "LED77") (pin "1") (pinfunction "VDD_1") (pintype "unspecified"))
      (node (ref "LED78") (pin "1") (pinfunction "VDD_1") (pintype "unspecified"))
      (node (ref "LED79") (pin "1") (pinfunction "VDD_1") (pintype "unspecified"))
      (node (ref "LED8") (pin "1") (pinfunction "VDD_1") (pintype "unspecified"))
      (node (ref "LED80") (pin "1") (pinfunction "VDD_1") (pintype "unspecified"))
      (node (ref "LED81") (pin "1") (pinfunction "VDD_1") (pintype "unspecified"))
      (node (ref "LED82") (pin "1") (pinfunction "VDD_1") (pintype "unspecified"))
      (node (ref "LED83") (pin "1") (pinfunction "VDD_1") (pintype "unspecified"))
      (node (ref "LED84") (pin "1") (pinfunction "VDD_1") (pintype "unspecified"))
      (node (ref "LED85") (pin "1") (pinfunction "VDD_1") (pintype "unspecified"))
      (node (ref "LED86") (pin "1") (pinfunction "VDD_1") (pintype "unspecified"))
      (node (ref "LED87") (pin "1") (pinfunction "VDD_1") (pintype "unspecified"))
      (node (ref "LED88") (pin "1") (pinfunction "VDD_1") (pintype "unspecified"))
      (node (ref "LED89") (pin "1") (pinfunction "VDD_1") (pintype "unspecified"))
      (node (ref "LED9") (pin "1") (pinfunction "VDD_1") (pintype "unspecified"))
      (node (ref "LED90") (pin "1") (pinfunction "VDD_1") (pintype "unspecified"))
      (node (ref "LED91") (pin "1") (pinfunction "VDD_1") (pintype "unspecified"))
      (node (ref "LED92") (pin "1") (pinfunction "VDD_1") (pintype "unspecified"))
      (node (ref "LED93") (pin "1") (pinfunction "VDD_1") (pintype "unspecified"))
      (node (ref "LED94") (pin "1") (pinfunction "VDD_1") (pintype "unspecified"))
      (node (ref "LED95") (pin "1") (pinfunction "VDD_1") (pintype "unspecified"))
      (node (ref "LED96") (pin "1") (pinfunction "VDD_1") (pintype "unspecified"))
      (node (ref "LED97") (pin "1") (pinfunction "VDD_1") (pintype "unspecified"))
      (node (ref "LED98") (pin "1") (pinfunction "VDD_1") (pintype "unspecified"))
      (node (ref "LED99") (pin "1") (pinfunction "VDD_1") (pintype "unspecified"))
    )
    (net (code "4") (name "Net-(LED2-DOU)") (class "Default")
      (node (ref "LED2") (pin "2") (pinfunction "DOU_2") (pintype "unspecified"))
      (node (ref "LED3") (pin "4") (pinfunction "DIN_4") (pintype "unspecified"))
    )
    (net (code "5") (name "Net-(LED3-DOU)") (class "Default")
      (node (ref "LED3") (pin "2") (pinfunction "DOU_2") (pintype "unspecified"))
      (node (ref "LED4") (pin "4") (pinfunction "DIN_4") (pintype "unspecified"))
    )
    (net (code "6") (name "Net-(LED4-DOU)") (class "Default")
      (node (ref "LED4") (pin "2") (pinfunction "DOU_2") (pintype "unspecified"))
      (node (ref "LED5") (pin "4") (pinfunction "DIN_4") (pintype "unspecified"))
    )
    (net (code "7") (name "Net-(LED5-DOU)") (class "Default")
      (node (ref "LED5") (pin "2") (pinfunction "DOU_2") (pintype "unspecified"))
      (node (ref "LED6") (pin "4") (pinfunction "DIN_4") (pintype "unspecified"))
    )
    (net (code "8") (name "Net-(LED6-DOU)") (class "Default")
      (node (ref "LED6") (pin "2") (pinfunction "DOU_2") (pintype "unspecified"))
      (node (ref "LED7") (pin "4") (pinfunction "DIN_4") (pintype "unspecified"))
    )
    (net (code "9") (name "Net-(LED7-DOU)") (class "Default")
      (node (ref "LED7") (pin "2") (pinfunction "DOU_2") (pintype "unspecified"))
      (node (ref "LED8") (pin "4") (pinfunction "DIN_4") (pintype "unspecified"))
    )
    (net (code "10") (name "Net-(LED8-DOU)") (class "Default")
      (node (ref "LED8") (pin "2") (pinfunction "DOU_2") (pintype "unspecified"))
      (node (ref "LED9") (pin "4") (pinfunction "DIN_4") (pintype "unspecified"))
    )
    (net (code "11") (name "Net-(LED10-DIN)") (class "Default")
      (node (ref "LED10") (pin "4") (pinfunction "DIN_4") (pintype "unspecified"))
      (node (ref "LED9") (pin "2") (pinfunction "DOU_2") (pintype "unspecified"))
    )
    (net (code "12") (name "Net-(LED10-DOU)") (class "Default")
      (node (ref "LED10") (pin "2") (pinfunction "DOU_2") (pintype "unspecified"))
      (node (ref "LED11") (pin "4") (pinfunction "DIN_4") (pintype "unspecified"))
    )
    (net (code "13") (name "Net-(LED11-DOU)") (class "Default")
      (node (ref "LED11") (pin "2") (pinfunction "DOU_2") (pintype "unspecified"))
      (node (ref "LED12") (pin "4") (pinfunction "DIN_4") (pintype "unspecified"))
    )
    (net (code "14") (name "Net-(LED12-DOU)") (class "Default")
      (node (ref "LED12") (pin "2") (pinfunction "DOU_2") (pintype "unspecified"))
      (node (ref "LED13") (pin "4") (pinfunction "DIN_4") (pintype "unspecified"))
    )
    (net (code "15") (name "Net-(LED13-DOU)") (class "Default")
      (node (ref "LED13") (pin "2") (pinfunction "DOU_2") (pintype "unspecified"))
      (node (ref "LED14") (pin "4") (pinfunction "DIN_4") (pintype "unspecified"))
    )
    (net (code "16") (name "Net-(LED14-DOU)") (class "Default")
      (node (ref "LED14") (pin "2") (pinfunction "DOU_2") (pintype "unspecified"))
      (node (ref "LED15") (pin "4") (pinfunction "DIN_4") (pintype "unspecified"))
    )
    (net (code "17") (name "Net-(LED15-DOU)") (class "Default")
      (node (ref "LED15") (pin "2") (pinfunction "DOU_2") (pintype "unspecified"))
      (node (ref "LED16") (pin "4") (pinfunction "DIN_4") (pintype "unspecified"))
    )
    (net (code "18") (name "Net-(LED16-DOU)") (class "Default")
      (node (ref "LED16") (pin "2") (pinfunction "DOU_2") (pintype "unspecified"))
      (node (ref "LED17") (pin "4") (pinfunction "DIN_4") (pintype "unspecified"))
    )
    (net (code "19") (name "Net-(LED17-DOU)") (class "Default")
      (node (ref "LED17") (pin "2") (pinfunction "DOU_2") (pintype "unspecified"))
      (node (ref "LED18") (pin "4") (pinfunction "DIN_4") (pintype "unspecified"))
    )
    (net (code "20") (name "Net-(LED18-DOU)") (class "Default")
      (node (ref "LED18") (pin "2") (pinfunction "DOU_2") (pintype "unspecified"))
      (node (ref "LED19") (pin "4") (pinfunction "DIN_4") (pintype "unspecified"))
    )
    (net (code "21") (name "Net-(LED19-DOU)") (class "Default")
      (node (ref "LED19") (pin "2") (pinfunction "DOU_2") (pintype "unspecified"))
      (node (ref "LED20") (pin "4") (pinfunction "DIN_4") (pintype "unspecified"))
    )
    (net (code "22") (name "Net-(LED20-DOU)") (class "Default")
      (node (ref "LED20") (pin "2") (pinfunction "DOU_2") (pintype "unspecified"))
      (node (ref "LED31") (pin "4") (pinfunction "DIN_4") (pintype "unspecified"))
    )
    (net (code "23") (name "Net-(LED21-DIN)") (class "Default")
      (node (ref "LED21") (pin "4") (pinfunction "DIN_4") (pintype "unspecified"))
      (node (ref "LED22") (pin "2") (pinfunction "DOU_2") (pintype "unspecified"))
    )
    (net (code "24") (name "Net-(LED21-DOU)") (class "Default")
      (node (ref "LED21") (pin "2") (pinfunction "DOU_2") (pintype "unspecified"))
      (node (ref "LED51") (pin "4") (pinfunction "DIN_4") (pintype "unspecified"))
    )
    (net (code "25") (name "Net-(LED22-DIN)") (class "Default")
      (node (ref "LED22") (pin "4") (pinfunction "DIN_4") (pintype "unspecified"))
      (node (ref "LED23") (pin "2") (pinfunction "DOU_2") (pintype "unspecified"))
    )
    (net (code "26") (name "Net-(LED23-DIN)") (class "Default")
      (node (ref "LED23") (pin "4") (pinfunction "DIN_4") (pintype "unspecified"))
      (node (ref "LED24") (pin "2") (pinfunction "DOU_2") (pintype "unspecified"))
    )
    (net (code "27") (name "Net-(LED24-DIN)") (class "Default")
      (node (ref "LED24") (pin "4") (pinfunction "DIN_4") (pintype "unspecified"))
      (node (ref "LED25") (pin "2") (pinfunction "DOU_2") (pintype "unspecified"))
    )
    (net (code "28") (name "Net-(LED25-DIN)") (class "Default")
      (node (ref "LED25") (pin "4") (pinfunction "DIN_4") (pintype "unspecified"))
      (node (ref "LED26") (pin "2") (pinfunction "DOU_2") (pintype "unspecified"))
    )
    (net (code "29") (name "Net-(LED26-DIN)") (class "Default")
      (node (ref "LED26") (pin "4") (pinfunction "DIN_4") (pintype "unspecified"))
      (node (ref "LED27") (pin "2") (pinfunction "DOU_2") (pintype "unspecified"))
    )
    (net (code "30") (name "Net-(LED27-DIN)") (class "Default")
      (node (ref "LED27") (pin "4") (pinfunction "DIN_4") (pintype "unspecified"))
      (node (ref "LED28") (pin "2") (pinfunction "DOU_2") (pintype "unspecified"))
    )
    (net (code "31") (name "Net-(LED28-DIN)") (class "Default")
      (node (ref "LED28") (pin "4") (pinfunction "DIN_4") (pintype "unspecified"))
      (node (ref "LED29") (pin "2") (pinfunction "DOU_2") (pintype "unspecified"))
    )
    (net (code "32") (name "Net-(LED29-DIN)") (class "Default")
      (node (ref "LED29") (pin "4") (pinfunction "DIN_4") (pintype "unspecified"))
      (node (ref "LED30") (pin "2") (pinfunction "DOU_2") (pintype "unspecified"))
    )
    (net (code "33") (name "Net-(LED30-DIN)") (class "Default")
      (node (ref "LED30") (pin "4") (pinfunction "DIN_4") (pintype "unspecified"))
      (node (ref "LED40") (pin "2") (pinfunction "DOU_2") (pintype "unspecified"))
    )
    (net (code "34") (name "Net-(LED31-DOU)") (class "Default")
      (node (ref "LED31") (pin "2") (pinfunction "DOU_2") (pintype "unspecified"))
      (node (ref "LED32") (pin "4") (pinfunction "DIN_4") (pintype "unspecified"))
    )
    (net (code "35") (name "Net-(LED32-DOU)") (class "Default")
      (node (ref "LED32") (pin "2") (pinfunction "DOU_2") (pintype "unspecified"))
      (node (ref "LED33") (pin "4") (pinfunction "DIN_4") (pintype "unspecified"))
    )
    (net (code "36") (name "Net-(LED33-DOU)") (class "Default")
      (node (ref "LED33") (pin "2") (pinfunction "DOU_2") (pintype "unspecified"))
      (node (ref "LED34") (pin "4") (pinfunction "DIN_4") (pintype "unspecified"))
    )
    (net (code "37") (name "Net-(LED34-DOU)") (class "Default")
      (node (ref "LED34") (pin "2") (pinfunction "DOU_2") (pintype "unspecified"))
      (node (ref "LED35") (pin "4") (pinfunction "DIN_4") (pintype "unspecified"))
    )
    (net (code "38") (name "Net-(LED35-DOU)") (class "Default")
      (node (ref "LED35") (pin "2") (pinfunction "DOU_2") (pintype "unspecified"))
      (node (ref "LED36") (pin "4") (pinfunction "DIN_4") (pintype "unspecified"))
    )
    (net (code "39") (name "Net-(LED36-DOU)") (class "Default")
      (node (ref "LED36") (pin "2") (pinfunction "DOU_2") (pintype "unspecified"))
      (node (ref "LED37") (pin "4") (pinfunction "DIN_4") (pintype "unspecified"))
    )
    (net (code "40") (name "Net-(LED37-DOU)") (class "Default")
      (node (ref "LED37") (pin "2") (pinfunction "DOU_2") (pintype "unspecified"))
      (node (ref "LED38") (pin "4") (pinfunction "DIN_4") (pintype "unspecified"))
    )
    (net (code "41") (name "Net-(LED38-DOU)") (class "Default")
      (node (ref "LED38") (pin "2") (pinfunction "DOU_2") (pintype "unspecified"))
      (node (ref "LED39") (pin "4") (pinfunction "DIN_4") (pintype "unspecified"))
    )
    (net (code "42") (name "Net-(LED39-DOU)") (class "Default")
      (node (ref "LED39") (pin "2") (pinfunction "DOU_2") (pintype "unspecified"))
      (node (ref "LED40") (pin "4") (pinfunction "DIN_4") (pintype "unspecified"))
    )
    (net (code "43") (name "Net-(LED41-DIN)") (class "Default")
      (node (ref "LED41") (pin "4") (pinfunction "DIN_4") (pintype "unspecified"))
      (node (ref "LED42") (pin "2") (pinfunction "DOU_2") (pintype "unspecified"))
    )
    (net (code "44") (name "Net-(LED41-DOU)") (class "Default")
      (node (ref "LED41") (pin "2") (pinfunction "DOU_2") (pintype "unspecified"))
      (node (ref "LED71") (pin "4") (pinfunction "DIN_4") (pintype "unspecified"))
    )
    (net (code "45") (name "Net-(LED42-DIN)") (class "Default")
      (node (ref "LED42") (pin "4") (pinfunction "DIN_4") (pintype "unspecified"))
      (node (ref "LED43") (pin "2") (pinfunction "DOU_2") (pintype "unspecified"))
    )
    (net (code "46") (name "Net-(LED43-DIN)") (class "Default")
      (node (ref "LED43") (pin "4") (pinfunction "DIN_4") (pintype "unspecified"))
      (node (ref "LED44") (pin "2") (pinfunction "DOU_2") (pintype "unspecified"))
    )
    (net (code "47") (name "Net-(LED44-DIN)") (class "Default")
      (node (ref "LED44") (pin "4") (pinfunction "DIN_4") (pintype "unspecified"))
      (node (ref "LED45") (pin "2") (pinfunction "DOU_2") (pintype "unspecified"))
    )
    (net (code "48") (name "Net-(LED45-DIN)") (class "Default")
      (node (ref "LED45") (pin "4") (pinfunction "DIN_4") (pintype "unspecified"))
      (node (ref "LED46") (pin "2") (pinfunction "DOU_2") (pintype "unspecified"))
    )
    (net (code "49") (name "Net-(LED46-DIN)") (class "Default")
      (node (ref "LED46") (pin "4") (pinfunction "DIN_4") (pintype "unspecified"))
      (node (ref "LED47") (pin "2") (pinfunction "DOU_2") (pintype "unspecified"))
    )
    (net (code "50") (name "Net-(LED47-DIN)") (class "Default")
      (node (ref "LED47") (pin "4") (pinfunction "DIN_4") (pintype "unspecified"))
      (node (ref "LED48") (pin "2") (pinfunction "DOU_2") (pintype "unspecified"))
    )
    (net (code "51") (name "Net-(LED48-DIN)") (class "Default")
      (node (ref "LED48") (pin "4") (pinfunction "DIN_4") (pintype "unspecified"))
      (node (ref "LED49") (pin "2") (pinfunction "DOU_2") (pintype "unspecified"))
    )
    (net (code "52") (name "Net-(LED49-DIN)") (class "Default")
      (node (ref "LED49") (pin "4") (pinfunction "DIN_4") (pintype "unspecified"))
      (node (ref "LED50") (pin "2") (pinfunction "DOU_2") (pintype "unspecified"))
    )
    (net (code "53") (name "Net-(LED50-DIN)") (class "Default")
      (node (ref "LED50") (pin "4") (pinfunction "DIN_4") (pintype "unspecified"))
      (node (ref "LED60") (pin "2") (pinfunction "DOU_2") (pintype "unspecified"))
    )
    (net (code "54") (name "Net-(LED51-DOU)") (class "Default")
      (node (ref "LED51") (pin "2") (pinfunction "DOU_2") (pintype "unspecified"))
      (node (ref "LED52") (pin "4") (pinfunction "DIN_4") (pintype "unspecified"))
    )
    (net (code "55") (name "Net-(LED52-DOU)") (class "Default")
      (node (ref "LED52") (pin "2") (pinfunction "DOU_2") (pintype "unspecified"))
      (node (ref "LED53") (pin "4") (pinfunction "DIN_4") (pintype "unspecified"))
    )
    (net (code "56") (name "Net-(LED53-DOU)") (class "Default")
      (node (ref "LED53") (pin "2") (pinfunction "DOU_2") (pintype "unspecified"))
      (node (ref "LED54") (pin "4") (pinfunction "DIN_4") (pintype "unspecified"))
    )
    (net (code "57") (name "Net-(LED54-DOU)") (class "Default")
      (node (ref "LED54") (pin "2") (pinfunction "DOU_2") (pintype "unspecified"))
      (node (ref "LED55") (pin "4") (pinfunction "DIN_4") (pintype "unspecified"))
    )
    (net (code "58") (name "Net-(LED55-DOU)") (class "Default")
      (node (ref "LED55") (pin "2") (pinfunction "DOU_2") (pintype "unspecified"))
      (node (ref "LED56") (pin "4") (pinfunction "DIN_4") (pintype "unspecified"))
    )
    (net (code "59") (name "Net-(LED56-DOU)") (class "Default")
      (node (ref "LED56") (pin "2") (pinfunction "DOU_2") (pintype "unspecified"))
      (node (ref "LED57") (pin "4") (pinfunction "DIN_4") (pintype "unspecified"))
    )
    (net (code "60") (name "Net-(LED57-DOU)") (class "Default")
      (node (ref "LED57") (pin "2") (pinfunction "DOU_2") (pintype "unspecified"))
      (node (ref "LED58") (pin "4") (pinfunction "DIN_4") (pintype "unspecified"))
    )
    (net (code "61") (name "Net-(LED58-DOU)") (class "Default")
      (node (ref "LED58") (pin "2") (pinfunction "DOU_2") (pintype "unspecified"))
      (node (ref "LED59") (pin "4") (pinfunction "DIN_4") (pintype "unspecified"))
    )
    (net (code "62") (name "Net-(LED59-DOU)") (class "Default")
      (node (ref "LED59") (pin "2") (pinfunction "DOU_2") (pintype "unspecified"))
      (node (ref "LED60") (pin "4") (pinfunction "DIN_4") (pintype "unspecified"))
    )
    (net (code "63") (name "Net-(LED61-DIN)") (class "Default")
      (node (ref "LED61") (pin "4") (pinfunction "DIN_4") (pintype "unspecified"))
      (node (ref "LED62") (pin "2") (pinfunction "DOU_2") (pintype "unspecified"))
    )
    (net (code "64") (name "Net-(LED61-DOU)") (class "Default")
      (node (ref "LED61") (pin "2") (pinfunction "DOU_2") (pintype "unspecified"))
      (node (ref "LED91") (pin "4") (pinfunction "DIN_4") (pintype "unspecified"))
    )
    (net (code "65") (name "Net-(LED62-DIN)") (class "Default")
      (node (ref "LED62") (pin "4") (pinfunction "DIN_4") (pintype "unspecified"))
      (node (ref "LED63") (pin "2") (pinfunction "DOU_2") (pintype "unspecified"))
    )
    (net (code "66") (name "Net-(LED63-DIN)") (class "Default")
      (node (ref "LED63") (pin "4") (pinfunction "DIN_4") (pintype "unspecified"))
      (node (ref "LED64") (pin "2") (pinfunction "DOU_2") (pintype "unspecified"))
    )
    (net (code "67") (name "Net-(LED64-DIN)") (class "Default")
      (node (ref "LED64") (pin "4") (pinfunction "DIN_4") (pintype "unspecified"))
      (node (ref "LED65") (pin "2") (pinfunction "DOU_2") (pintype "unspecified"))
    )
    (net (code "68") (name "Net-(LED65-DIN)") (class "Default")
      (node (ref "LED65") (pin "4") (pinfunction "DIN_4") (pintype "unspecified"))
      (node (ref "LED66") (pin "2") (pinfunction "DOU_2") (pintype "unspecified"))
    )
    (net (code "69") (name "Net-(LED66-DIN)") (class "Default")
      (node (ref "LED66") (pin "4") (pinfunction "DIN_4") (pintype "unspecified"))
      (node (ref "LED67") (pin "2") (pinfunction "DOU_2") (pintype "unspecified"))
    )
    (net (code "70") (name "Net-(LED67-DIN)") (class "Default")
      (node (ref "LED67") (pin "4") (pinfunction "DIN_4") (pintype "unspecified"))
      (node (ref "LED68") (pin "2") (pinfunction "DOU_2") (pintype "unspecified"))
    )
    (net (code "71") (name "Net-(LED68-DIN)") (class "Default")
      (node (ref "LED68") (pin "4") (pinfunction "DIN_4") (pintype "unspecified"))
      (node (ref "LED69") (pin "2") (pinfunction "DOU_2") (pintype "unspecified"))
    )
    (net (code "72") (name "Net-(LED69-DIN)") (class "Default")
      (node (ref "LED69") (pin "4") (pinfunction "DIN_4") (pintype "unspecified"))
      (node (ref "LED70") (pin "2") (pinfunction "DOU_2") (pintype "unspecified"))
    )
    (net (code "73") (name "Net-(LED70-DIN)") (class "Default")
      (node (ref "LED70") (pin "4") (pinfunction "DIN_4") (pintype "unspecified"))
      (node (ref "LED80") (pin "2") (pinfunction "DOU_2") (pintype "unspecified"))
    )
    (net (code "74") (name "Net-(LED71-DOU)") (class "Default")
      (node (ref "LED71") (pin "2") (pinfunction "DOU_2") (pintype "unspecified"))
      (node (ref "LED72") (pin "4") (pinfunction "DIN_4") (pintype "unspecified"))
    )
    (net (code "75") (name "Net-(LED72-DOU)") (class "Default")
      (node (ref "LED72") (pin "2") (pinfunction "DOU_2") (pintype "unspecified"))
      (node (ref "LED73") (pin "4") (pinfunction "DIN_4") (pintype "unspecified"))
    )
    (net (code "76") (name "Net-(LED73-DOU)") (class "Default")
      (node (ref "LED73") (pin "2") (pinfunction "DOU_2") (pintype "unspecified"))
      (node (ref "LED74") (pin "4") (pinfunction "DIN_4") (pintype "unspecified"))
    )
    (net (code "77") (name "Net-(LED74-DOU)") (class "Default")
      (node (ref "LED74") (pin "2") (pinfunction "DOU_2") (pintype "unspecified"))
      (node (ref "LED75") (pin "4") (pinfunction "DIN_4") (pintype "unspecified"))
    )
    (net (code "78") (name "Net-(LED75-DOU)") (class "Default")
      (node (ref "LED75") (pin "2") (pinfunction "DOU_2") (pintype "unspecified"))
      (node (ref "LED76") (pin "4") (pinfunction "DIN_4") (pintype "unspecified"))
    )
    (net (code "79") (name "Net-(LED76-DOU)") (class "Default")
      (node (ref "LED76") (pin "2") (pinfunction "DOU_2") (pintype "unspecified"))
      (node (ref "LED77") (pin "4") (pinfunction "DIN_4") (pintype "unspecified"))
    )
    (net (code "80") (name "Net-(LED77-DOU)") (class "Default")
      (node (ref "LED77") (pin "2") (pinfunction "DOU_2") (pintype "unspecified"))
      (node (ref "LED78") (pin "4") (pinfunction "DIN_4") (pintype "unspecified"))
    )
    (net (code "81") (name "Net-(LED78-DOU)") (class "Default")
      (node (ref "LED78") (pin "2") (pinfunction "DOU_2") (pintype "unspecified"))
      (node (ref "LED79") (pin "4") (pinfunction "DIN_4") (pintype "unspecified"))
    )
    (net (code "82") (name "Net-(LED79-DOU)") (class "Default")
      (node (ref "LED79") (pin "2") (pinfunction "DOU_2") (pintype "unspecified"))
      (node (ref "LED80") (pin "4") (pinfunction "DIN_4") (pintype "unspecified"))
    )
    (net (code "83") (name "Net-(LED81-DIN)") (class "Default")
      (node (ref "LED81") (pin "4") (pinfunction "DIN_4") (pintype "unspecified"))
      (node (ref "LED82") (pin "2") (pinfunction "DOU_2") (pintype "unspecified"))
    )
    (net (code "84") (name "Net-(LED82-DIN)") (class "Default")
      (node (ref "LED82") (pin "4") (pinfunction "DIN_4") (pintype "unspecified"))
      (node (ref "LED83") (pin "2") (pinfunction "DOU_2") (pintype "unspecified"))
    )
    (net (code "85") (name "Net-(LED83-DIN)") (class "Default")
      (node (ref "LED83") (pin "4") (pinfunction "DIN_4") (pintype "unspecified"))
      (node (ref "LED84") (pin "2") (pinfunction "DOU_2") (pintype "unspecified"))
    )
    (net (code "86") (name "Net-(LED84-DIN)") (class "Default")
      (node (ref "LED84") (pin "4") (pinfunction "DIN_4") (pintype "unspecified"))
      (node (ref "LED85") (pin "2") (pinfunction "DOU_2") (pintype "unspecified"))
    )
    (net (code "87") (name "Net-(LED85-DIN)") (class "Default")
      (node (ref "LED85") (pin "4") (pinfunction "DIN_4") (pintype "unspecified"))
      (node (ref "LED86") (pin "2") (pinfunction "DOU_2") (pintype "unspecified"))
    )
    (net (code "88") (name "Net-(LED86-DIN)") (class "Default")
      (node (ref "LED86") (pin "4") (pinfunction "DIN_4") (pintype "unspecified"))
      (node (ref "LED87") (pin "2") (pinfunction "DOU_2") (pintype "unspecified"))
    )
    (net (code "89") (name "Net-(LED87-DIN)") (class "Default")
      (node (ref "LED87") (pin "4") (pinfunction "DIN_4") (pintype "unspecified"))
      (node (ref "LED88") (pin "2") (pinfunction "DOU_2") (pintype "unspecified"))
    )
    (net (code "90") (name "Net-(LED88-DIN)") (class "Default")
      (node (ref "LED88") (pin "4") (pinfunction "DIN_4") (pintype "unspecified"))
      (node (ref "LED89") (pin "2") (pinfunction "DOU_2") (pintype "unspecified"))
    )
    (net (code "91") (name "Net-(LED89-DIN)") (class "Default")
      (node (ref "LED89") (pin "4") (pinfunction "DIN_4") (pintype "unspecified"))
      (node (ref "LED90") (pin "2") (pinfunction "DOU_2") (pintype "unspecified"))
    )
    (net (code "92") (name "Net-(LED91-DOU)") (class "Default")
      (node (ref "LED91") (pin "2") (pinfunction "DOU_2") (pintype "unspecified"))
      (node (ref "LED92") (pin "4") (pinfunction "DIN_4") (pintype "unspecified"))
    )
    (net (code "93") (name "Net-(LED92-DOU)") (class "Default")
      (node (ref "LED92") (pin "2") (pinfunction "DOU_2") (pintype "unspecified"))
      (node (ref "LED93") (pin "4") (pinfunction "DIN_4") (pintype "unspecified"))
    )
    (net (code "94") (name "Net-(LED93-DOU)") (class "Default")
      (node (ref "LED93") (pin "2") (pinfunction "DOU_2") (pintype "unspecified"))
      (node (ref "LED94") (pin "4") (pinfunction "DIN_4") (pintype "unspecified"))
    )
    (net (code "95") (name "Net-(LED94-DOU)") (class "Default")
      (node (ref "LED94") (pin "2") (pinfunction "DOU_2") (pintype "unspecified"))
      (node (ref "LED95") (pin "4") (pinfunction "DIN_4") (pintype "unspecified"))
    )
    (net (code "96") (name "Net-(LED95-DOU)") (class "Default")
      (node (ref "LED95") (pin "2") (pinfunction "DOU_2") (pintype "unspecified"))
      (node (ref "LED96") (pin "4") (pinfunction "DIN_4") (pintype "unspecified"))
    )
    (net (code "97") (name "Net-(LED96-DOU)") (class "Default")
      (node (ref "LED96") (pin "2") (pinfunction "DOU_2") (pintype "unspecified"))
      (node (ref "LED97") (pin "4") (pinfunction "DIN_4") (pintype "unspecified"))
    )
    (net (code "98") (name "Net-(LED97-DOU)") (class "Default")
      (node (ref "LED97") (pin "2") (pinfunction "DOU_2") (pintype "unspecified"))
      (node (ref "LED98") (pin "4") (pinfunction "DIN_4") (pintype "unspecified"))
    )
    (net (code "99") (name "Net-(LED98-DOU)") (class "Default")
      (node (ref "LED98") (pin "2") (pinfunction "DOU_2") (pintype "unspecified"))
      (node (ref "LED99") (pin "4") (pinfunction "DIN_4") (pintype "unspecified"))
    )
    (net (code "100") (name "Net-(LED100-DIN)") (class "Default")
      (node (ref "LED100") (pin "4") (pinfunction "DIN_4") (pintype "unspecified"))
      (node (ref "LED99") (pin "2") (pinfunction "DOU_2") (pintype "unspecified"))
    )
    (net (code "101") (name "Net-(LED100-DOU)") (class "Default")
      (node (ref "LED100") (pin "2") (pinfunction "DOU_2") (pintype "unspecified"))
      (node (ref "LED90") (pin "4") (pinfunction "DIN_4") (pintype "unspecified"))
    )
    (net (code "102") (name "unconnected-(LED1-DIN-Pad4)") (class "Default")
      (node (ref "LED1") (pin "4") (pinfunction "DIN_4") (pintype "unspecified"))
    )
    (net (code "103") (name "unconnected-(LED81-DOU-Pad2)") (class "Default")
      (node (ref "LED81") (pin "2") (pinfunction "DOU_2") (pintype "unspecified"))
    )
  )
)
